# Archer.net
KiCad netlist of a schematic drawn in Altium Designer
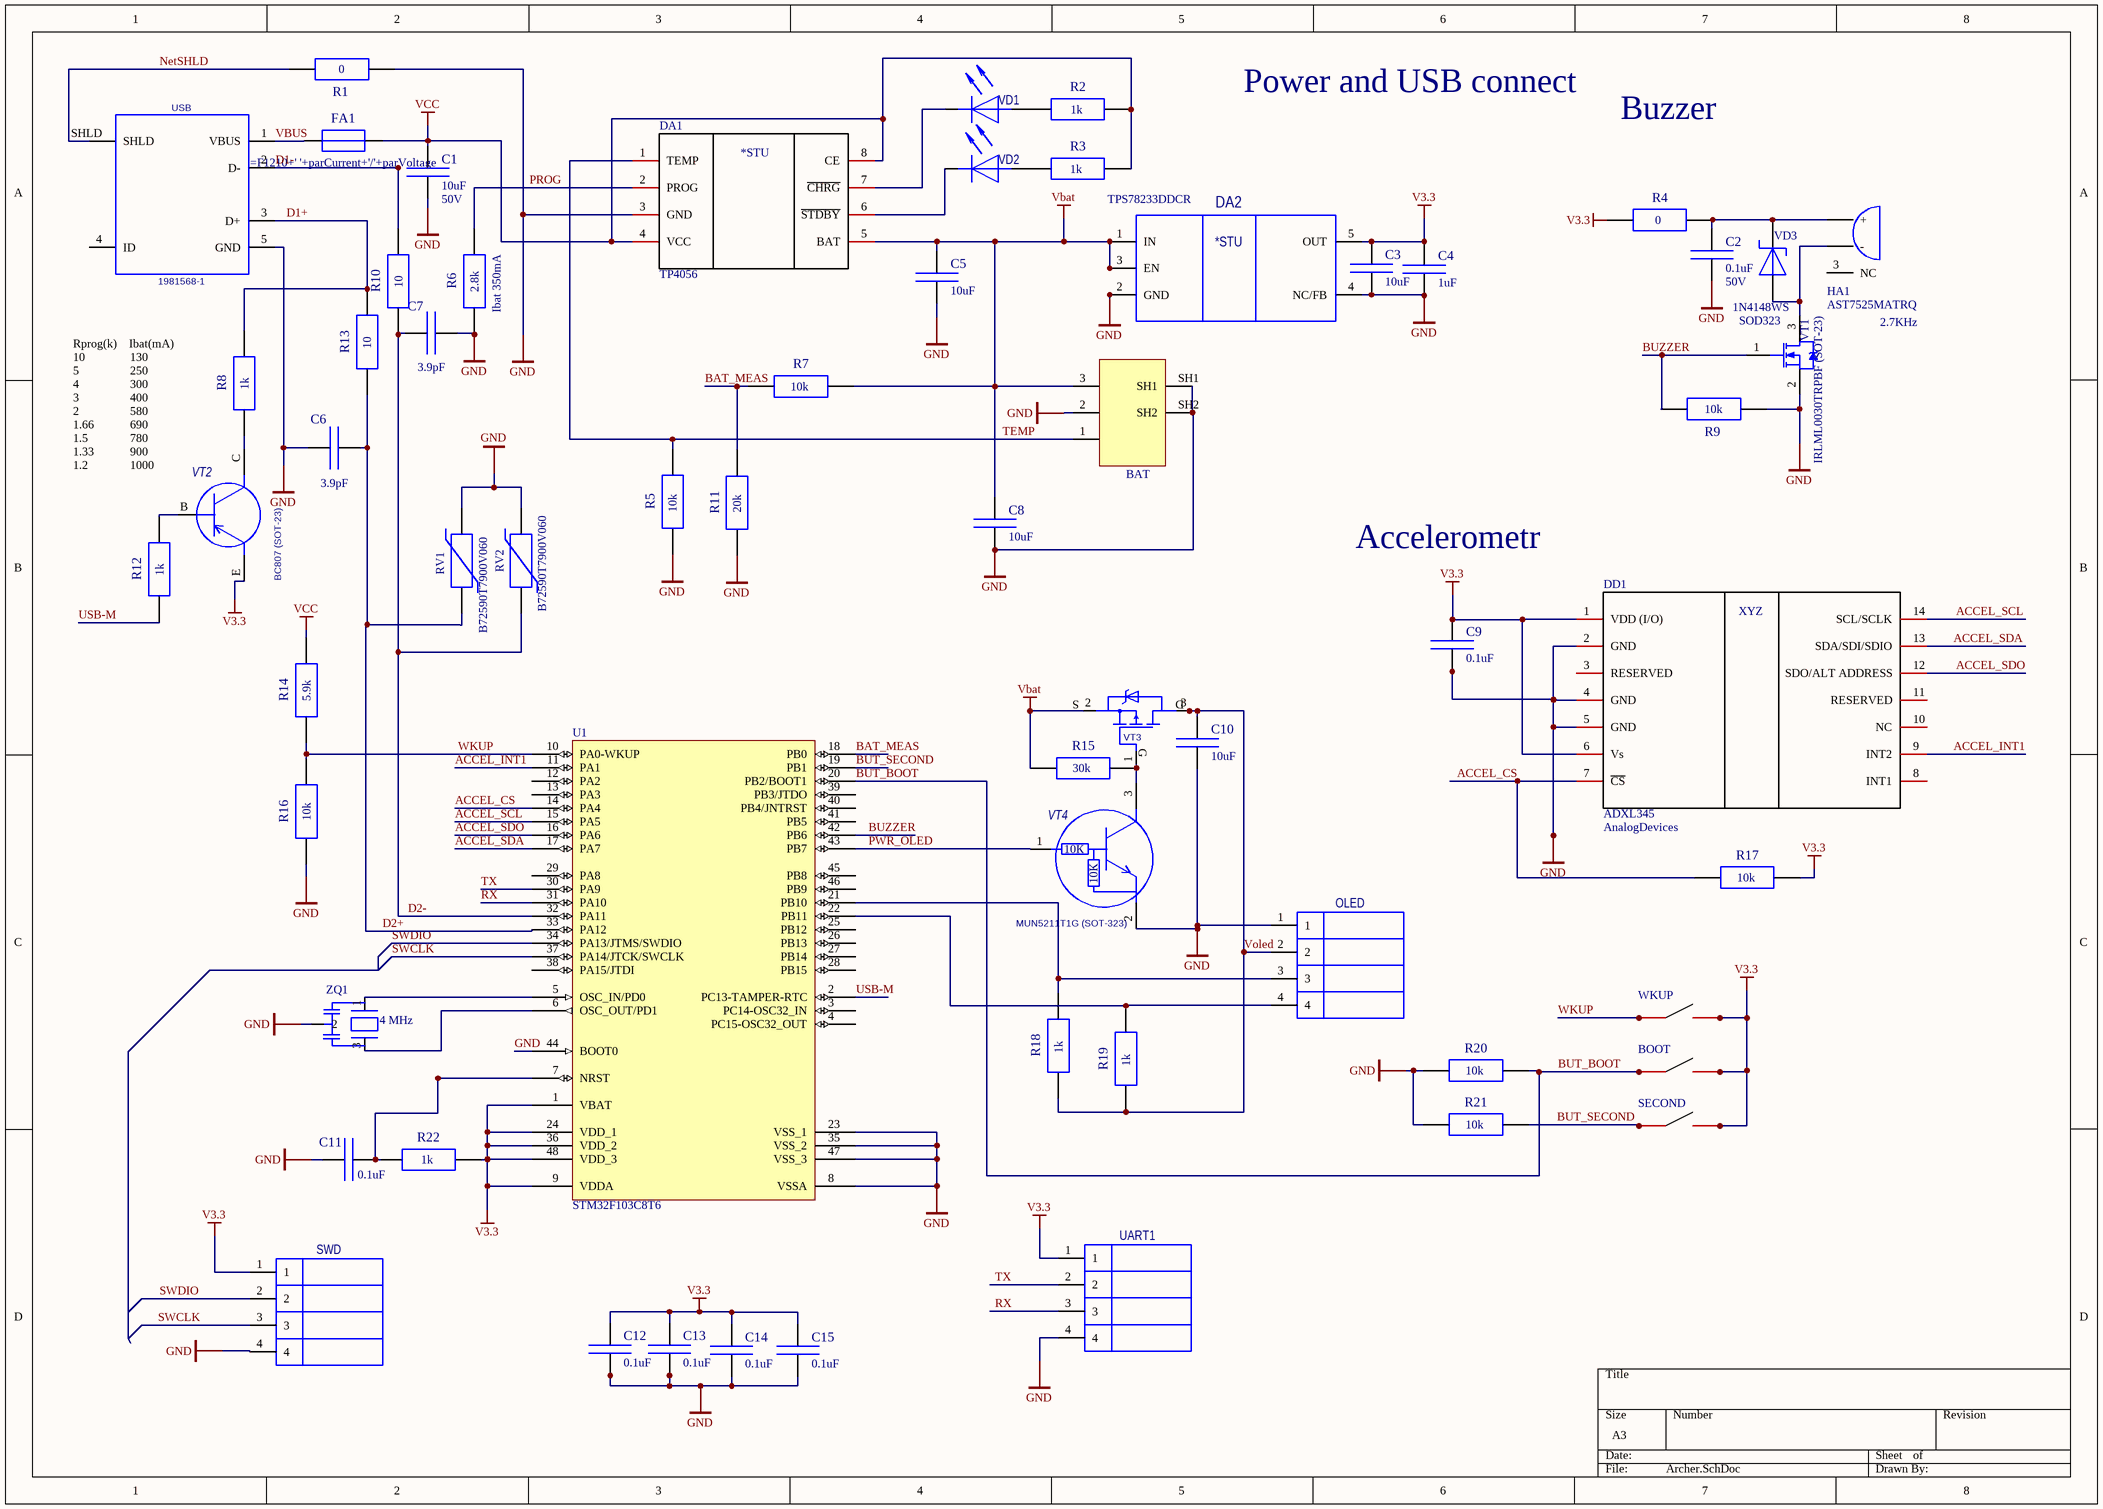
[diagram p0: Archer.SchDoc]

(export (version "E")
  (design (tool "Eeschema 10.0.6"))
  (components
    (comp (ref "BAT")
      (value "Hirose DF13A-3P-1.25H(20)")
      (footprint "DF13A-3P-1.25H")
      (description "Crimping Connector 3p")
      (fields (field (name "CMPPARTNUM") "DF13A-3P-1.25H(20)"))
      (libsource (lib "connectors") (part "DF13C-3P-1.25_(**)"))
    )
    (comp (ref "BOOT")
      (value "~")
      (footprint "Button Switronic Industrial 0650HIM-130G-G high")
      (description "Кнопка тактовая без фиксации")
      (libsource (lib "RADIOMASTER") (part "Button Switronic Industrial 0650HIM-130G-G high"))
    )
    (comp (ref "C1")
      (value "10uF")
      (footprint "CAPC3216X135(1206)")
      (description "C1206")
      (fields (field (name "PARVOLTAGE") "50V") (field (name "Comment") "чип 1206 10uF/50V, "))
      (libsource (lib "pass_smd") (part "C1206"))
    )
    (comp (ref "C2")
      (value "0.1uF")
      (footprint "CAPC1608X50(0603)")
      (description "C0603")
      (fields (field (name "PARVOLTAGE") "50V") (field (name "Comment") "чип 0603 0.1uF/50V, "))
      (libsource (lib "pass_smd") (part "C0603"))
    )
    (comp (ref "C3")
      (value "10uF")
      (footprint "CAPC3216X135(1206)")
      (description "C1206")
      (fields (field (name "Comment") "чип 1206 10uF/50V, "))
      (libsource (lib "pass_smd") (part "C1206"))
    )
    (comp (ref "C4")
      (value "1uF")
      (footprint "CAPC1608X50(0603)")
      (description "C0603")
      (fields (field (name "Comment") "чип 0603 1uF/50V, "))
      (libsource (lib "pass_smd") (part "C0603"))
    )
    (comp (ref "C5")
      (value "10uF")
      (footprint "CAPC3216X135(1206)")
      (description "C1206")
      (fields (field (name "Comment") "чип 1206 10uF/50V, "))
      (libsource (lib "pass_smd") (part "C1206"))
    )
    (comp (ref "C6")
      (value "3.9pF")
      (footprint "CAPC1608X50(0603)")
      (description "C0603")
      (fields (field (name "Comment") "чип 0603 3.9pF/50V, "))
      (libsource (lib "pass_smd") (part "C0603"))
    )
    (comp (ref "C7")
      (value "3.9pF")
      (footprint "CAPC1608X50(0603)")
      (description "C0603")
      (fields (field (name "Comment") "чип 0603 3.9pF/50V, "))
      (libsource (lib "pass_smd") (part "C0603"))
    )
    (comp (ref "C8")
      (value "10uF")
      (footprint "CAPC3216X135(1206)")
      (description "C1206")
      (fields (field (name "Comment") "чип 1206 10uF/50V, "))
      (libsource (lib "pass_smd") (part "C1206"))
    )
    (comp (ref "C9")
      (value "0.1uF")
      (footprint "CAPC1608X50(0603)")
      (description "C0603")
      (fields (field (name "Comment") "чип 0603 0.1uF/50V, "))
      (libsource (lib "pass_smd") (part "C0603"))
    )
    (comp (ref "C10")
      (value "10uF")
      (footprint "CAPC2012X135(0805)")
      (description "C0805")
      (fields (field (name "Comment") "чип 0805 10uF/50V, "))
      (libsource (lib "pass_smd") (part "C0805"))
    )
    (comp (ref "C11")
      (value "0.1uF")
      (footprint "CAPC1608X50(0603)")
      (description "C0603")
      (fields (field (name "Comment") "чип 0603 0.1uF/50V, "))
      (libsource (lib "pass_smd") (part "C0603"))
    )
    (comp (ref "C12")
      (value "0.1uF")
      (footprint "CAPC1608X50(0603)")
      (description "C0603")
      (fields (field (name "Comment") "чип 0603 0.1uF/50V, "))
      (libsource (lib "pass_smd") (part "C0603"))
    )
    (comp (ref "C13")
      (value "0.1uF")
      (footprint "CAPC1608X50(0603)")
      (description "C0603")
      (fields (field (name "Comment") "чип 0603 0.1uF/50V, "))
      (libsource (lib "pass_smd") (part "C0603"))
    )
    (comp (ref "C14")
      (value "0.1uF")
      (footprint "CAPC1608X50(0603)")
      (description "C0603")
      (fields (field (name "Comment") "чип 0603 0.1uF/50V, "))
      (libsource (lib "pass_smd") (part "C0603"))
    )
    (comp (ref "C15")
      (value "0.1uF")
      (footprint "CAPC1608X50(0603)")
      (description "C0603")
      (fields (field (name "Comment") "чип 0603 0.1uF/50V, "))
      (libsource (lib "pass_smd") (part "C0603"))
    )
    (comp (ref "DA1")
      (value "~")
      (footprint "Microchip NanJing Linear Battery Charger TP4056 SOP-8")
      (fields (field (name "MODEL NAME") "TP4056"))
      (libsource (lib "RADIOMASTER") (part "Microchip NanJing Linear Battery Charger TP4056 SOP-8"))
    )
    (comp (ref "DA2")
      (value "TPS78233DDCR(SOT23-5)")
      (footprint "SOT95P285X130-5N(SOT23-5)")
      (description "TPS76333DBV")
      (fields (field (name "CMPPARTNUM") "TPS78233DDCR"))
      (libsource (lib "TI") (part "TPS76333DBV"))
    )
    (comp (ref "DD1")
      (value "~")
      (footprint "Microchip DigitalAccelerometer AnalogDevices ADXL345 LGA-14")
      (fields (field (name "MODEL NAME") "ADXL345") (field (name "FACTORY") "AnalogDevices"))
      (libsource (lib "RADIOMASTER") (part "Microchip DigitalAccelerometer AnalogDevices ADXL345 LGA-14"))
    )
    (comp (ref "FA1")
      (value "2A/")
      (footprint "RESC1210N")
      (description "FUSE 1210")
      (libsource (lib "pass_smd") (part "FUSE 1210"))
    )
    (comp (ref "HA1")
      (value "AST7525MATRQ")
      (footprint "AST7525MATRQ")
      (description "Transducer (Electro-Mech)")
      (fields (field (name "ПРИМЕЧАНИЕ") "2.7KHz"))
      (libsource (lib "MyLib") (part "AST7525MATRQ"))
    )
    (comp (ref "OLED")
      (value "DS1021-1x4")
      (footprint "HDRV4P254_1x4")
      (description "IDC разъем 4 контактов. Шаг 2.54мм")
      (libsource (lib "connectors") (part "Header-2.54P-4N"))
    )
    (comp (ref "R1")
      (value "0")
      (footprint "RESC1608X45(0603)")
      (description "R0603")
      (fields (field (name "TOLERANCE") "5%") (field (name "Comment") "чип 0603 0 5%"))
      (libsource (lib "pass_smd") (part "R0603"))
    )
    (comp (ref "R2")
      (value "1k")
      (footprint "RESC1608X45(0603)")
      (description "R0603")
      (fields (field (name "TOLERANCE") "5%") (field (name "Comment") "чип 0603 1k 5%"))
      (libsource (lib "pass_smd") (part "R0603"))
    )
    (comp (ref "R3")
      (value "1k")
      (footprint "RESC1608X45(0603)")
      (description "R0603")
      (fields (field (name "TOLERANCE") "5%") (field (name "Comment") "чип 0603 1k 5%"))
      (libsource (lib "pass_smd") (part "R0603"))
    )
    (comp (ref "R4")
      (value "0")
      (footprint "RESC1608X45(0603)")
      (description "R0603")
      (fields (field (name "TOLERANCE") "5%") (field (name "Comment") "чип 0603 0 5%"))
      (libsource (lib "pass_smd") (part "R0603"))
    )
    (comp (ref "R5")
      (value "10k")
      (footprint "RESC1608X45(0603)")
      (description "R0603")
      (fields (field (name "TOLERANCE") "5%") (field (name "Comment") "чип 0603 10k 5%"))
      (libsource (lib "pass_smd") (part "R0603"))
    )
    (comp (ref "R6")
      (value "2.8k")
      (footprint "RESC1608X45(0603)")
      (description "R0603")
      (fields (field (name "TOLERANCE") "5%") (field (name "Comment") "чип 0603 2.8k 5%"))
      (libsource (lib "pass_smd") (part "R0603"))
    )
    (comp (ref "R7")
      (value "10k")
      (footprint "RESC1608X45(0603)")
      (description "R0603")
      (fields (field (name "TOLERANCE") "5%") (field (name "Comment") "чип 0603 10k 5%"))
      (libsource (lib "pass_smd") (part "R0603"))
    )
    (comp (ref "R8")
      (value "1k")
      (footprint "RESC1608X45(0603)")
      (description "R0603")
      (fields (field (name "TOLERANCE") "5%") (field (name "Comment") "чип 0603 1k 5%"))
      (libsource (lib "pass_smd") (part "R0603"))
    )
    (comp (ref "R9")
      (value "10k")
      (footprint "RESC1608X45(0603)")
      (description "R0603")
      (fields (field (name "TOLERANCE") "5%") (field (name "Comment") "чип 0603 10k 5%"))
      (libsource (lib "pass_smd") (part "R0603"))
    )
    (comp (ref "R10")
      (value "10")
      (footprint "RESC1608X45(0603)")
      (description "R0603")
      (fields (field (name "TOLERANCE") "5%") (field (name "Comment") "чип 0603 10 5%"))
      (libsource (lib "pass_smd") (part "R0603"))
    )
    (comp (ref "R11")
      (value "20k")
      (footprint "RESC1608X45(0603)")
      (description "R0603")
      (fields (field (name "TOLERANCE") "5%") (field (name "Comment") "чип 0603 20k 5%"))
      (libsource (lib "pass_smd") (part "R0603"))
    )
    (comp (ref "R12")
      (value "1k")
      (footprint "RESC1608X45(0603)")
      (description "R0603")
      (fields (field (name "TOLERANCE") "5%") (field (name "Comment") "чип 0603 1k 5%"))
      (libsource (lib "pass_smd") (part "R0603"))
    )
    (comp (ref "R13")
      (value "10")
      (footprint "RESC1608X45(0603)")
      (description "R0603")
      (fields (field (name "TOLERANCE") "5%") (field (name "Comment") "чип 0603 10 5%"))
      (libsource (lib "pass_smd") (part "R0603"))
    )
    (comp (ref "R14")
      (value "5.9k")
      (footprint "RESC1608X45(0603)")
      (description "R0603")
      (fields (field (name "TOLERANCE") "5%") (field (name "Comment") "чип 0603 5.9k 5%"))
      (libsource (lib "pass_smd") (part "R0603"))
    )
    (comp (ref "R15")
      (value "30k")
      (footprint "RESC1608X45(0603)")
      (description "R0603")
      (fields (field (name "TOLERANCE") "5%") (field (name "Comment") "чип 0603 30k 5%"))
      (libsource (lib "pass_smd") (part "R0603"))
    )
    (comp (ref "R16")
      (value "10k")
      (footprint "RESC1608X45(0603)")
      (description "R0603")
      (fields (field (name "TOLERANCE") "5%") (field (name "Comment") "чип 0603 10k 5%"))
      (libsource (lib "pass_smd") (part "R0603"))
    )
    (comp (ref "R17")
      (value "10k")
      (footprint "RESC1608X45(0603)")
      (description "R0603")
      (fields (field (name "TOLERANCE") "5%") (field (name "Comment") "чип 0603 10k 5%"))
      (libsource (lib "pass_smd") (part "R0603"))
    )
    (comp (ref "R18")
      (value "1k")
      (footprint "RESC1608X45(0603)")
      (description "R0603")
      (fields (field (name "TOLERANCE") "5%") (field (name "Comment") "чип 0603 1k 5%"))
      (libsource (lib "pass_smd") (part "R0603"))
    )
    (comp (ref "R19")
      (value "1k")
      (footprint "RESC1608X45(0603)")
      (description "R0603")
      (fields (field (name "TOLERANCE") "5%") (field (name "Comment") "чип 0603 1k 5%"))
      (libsource (lib "pass_smd") (part "R0603"))
    )
    (comp (ref "R20")
      (value "10k")
      (footprint "RESC1608X45(0603)")
      (description "R0603")
      (fields (field (name "TOLERANCE") "5%") (field (name "Comment") "чип 0603 10k 5%"))
      (libsource (lib "pass_smd") (part "R0603"))
    )
    (comp (ref "R21")
      (value "10k")
      (footprint "RESC1608X45(0603)")
      (description "R0603")
      (fields (field (name "TOLERANCE") "5%") (field (name "Comment") "чип 0603 10k 5%"))
      (libsource (lib "pass_smd") (part "R0603"))
    )
    (comp (ref "R22")
      (value "1k")
      (footprint "RESC1608X45(0603)")
      (description "R0603")
      (fields (field (name "TOLERANCE") "5%") (field (name "Comment") "чип 0603 1k 5%"))
      (libsource (lib "pass_smd") (part "R0603"))
    )
    (comp (ref "RV1")
      (value "B72590T7900V060")
      (footprint "RESC1005X35(0402)")
      (libsource (lib "pass_smd") (part "B72590T7900V060"))
    )
    (comp (ref "RV2")
      (value "B72590T7900V060")
      (footprint "RESC1005X35(0402)")
      (libsource (lib "pass_smd") (part "B72590T7900V060"))
    )
    (comp (ref "SECOND")
      (value "~")
      (footprint "Button Switronic Industrial 0650HIM-130G-G high")
      (description "Кнопка тактовая без фиксации")
      (libsource (lib "RADIOMASTER") (part "Button Switronic Industrial 0650HIM-130G-G high"))
    )
    (comp (ref "SWD")
      (value "DS1021-1x4")
      (footprint "HDRV4P254_1x4")
      (description "IDC разъем 4 контактов. Шаг 2.54мм")
      (libsource (lib "connectors") (part "Header-2.54P-4N"))
    )
    (comp (ref "U1")
      (value "STM32F103C8T6")
      (footprint "LQFP48_N")
      (description "STM32 ARM-based 32-bit MCU with 64 Kbytes Flash, 48-pin LQFP, Industrial Temperature")
      (fields (field (name "PUBLISHER") "Altium Limited"))
      (libsource (lib "ST Microcontroller 32-Bit STM32") (part "STM32F103C8T6"))
    )
    (comp (ref "UART1")
      (value "DS1021-1x4")
      (footprint "HDRV4P254_1x4")
      (description "IDC разъем 4 контактов. Шаг 2.54мм")
      (libsource (lib "connectors") (part "Header-2.54P-4N"))
    )
    (comp (ref "USB")
      (value "1981568-1")
      (footprint "USB MICRO-B")
      (description "USB micro type A. SMT (TE 1981568-1)")
      (libsource (lib "connectors") (part "USB Micro-B Tyco"))
    )
    (comp (ref "VD1")
      (value "чип 0603 LED (RED)")
      (footprint "LEDC1608X80N(0603)_red")
      (description "LED 0603")
      (libsource (lib "diodes") (part "LED 0603"))
    )
    (comp (ref "VD2")
      (value "чип 0603 LED (RED)")
      (footprint "LEDC1608X80N(0603)_red")
      (description "LED 0603")
      (libsource (lib "diodes") (part "LED 0603"))
    )
    (comp (ref "VD3")
      (value "1N4148WS (SOD323)")
      (footprint "SOD2514X110N(SOD323)")
      (description "BAT54WS")
      (fields (field (name "CMPPKG") "SOD323") (field (name "CMPPARTNUM") "1N4148WS"))
      (libsource (lib "diodes") (part "SOD323 SCHOTTKY"))
    )
    (comp (ref "VT1")
      (value "IRLML0030TRPBF (SOT-23)")
      (footprint "SOT95P230-3N (SOT-23) num")
      (description "HEXFET Power MOSFET")
      (fields (field (name "CMPPARTNUM") "IRLML0030TRPBF"))
      (libsource (lib "transistors") (part "IRLML0030"))
    )
    (comp (ref "VT2")
      (value "BC807 (SOT-23)")
      (footprint "SOT95P230-3N (SOT-23)")
      (description "BC807")
      (libsource (lib "transistors") (part "BC807"))
    )
    (comp (ref "VT3")
      (value "IRLML6402TRPBF (SOT-23)")
      (footprint "SOT95P230-3N (SOT-23) num")
      (description "IRLML6402")
      (fields (field (name "CMPPARTNUM") "IRLML6402TRPBF"))
      (libsource (lib "transistors") (part "IRLML6402"))
    )
    (comp (ref "VT4")
      (value "MUN5211T1G (SOT-323)")
      (footprint "SOT65P200X110-3N (SOT323)_NUM")
      (description "MUN5211T1")
      (fields
        (field (name "CMPPARTNUM") "MUN5211T1G")
        (field (name "PARR1VALUE") "10К")
        (field (name "PARR2VALUE") "10К")
      )
      (libsource (lib "transistors") (part "MUN5211T1G"))
    )
    (comp (ref "WKUP")
      (value "~")
      (footprint "Button Switronic Industrial 0650HIM-130G-G high")
      (description "Кнопка тактовая без фиксации")
      (libsource (lib "RADIOMASTER") (part "Button Switronic Industrial 0650HIM-130G-G high"))
    )
    (comp (ref "ZQ1")
      (value "4 MHz")
      (footprint "XTAL450X200X120 (CSTCR)")
      (description "CSTCR_G15C Ceramic Resonators")
      (fields (field (name "CMPPARTNUM") "CSTCR4M00G53Z-B0") (field (name "TOLERANCE") "±0.5%"))
      (libsource (lib "xtal") (part "XTAL, SMD, 4.5mm x 2mm, 3 pads"))
    )
  )
  (nets
    (net (code "1") (name "/ACCEL_CS") (class "Default")
      (node (ref "DD1") (pin "7") (pinfunction "~{CS}_7") (pintype "passive"))
      (node (ref "R17") (pin "1") (pinfunction "1_1") (pintype "passive"))
      (node (ref "U1") (pin "14") (pinfunction "PA4_14") (pintype "bidirectional"))
    )
    (net (code "2") (name "/ACCEL_INT1") (class "Default")
      (node (ref "DD1") (pin "9") (pinfunction "INT2_9") (pintype "passive"))
      (node (ref "U1") (pin "11") (pinfunction "PA1_11") (pintype "bidirectional"))
    )
    (net (code "3") (name "/ACCEL_SCL") (class "Default")
      (node (ref "DD1") (pin "14") (pinfunction "SCL/SCLK_14") (pintype "passive"))
      (node (ref "U1") (pin "15") (pinfunction "PA5_15") (pintype "bidirectional"))
    )
    (net (code "4") (name "/ACCEL_SDA") (class "Default")
      (node (ref "DD1") (pin "13") (pinfunction "SDA/SDI/SDIO_13") (pintype "passive"))
      (node (ref "U1") (pin "17") (pinfunction "PA7_17") (pintype "bidirectional"))
    )
    (net (code "5") (name "/ACCEL_SDO") (class "Default")
      (node (ref "DD1") (pin "12") (pinfunction "SDO/ALT_ADDRESS_12") (pintype "passive"))
      (node (ref "U1") (pin "16") (pinfunction "PA6_16") (pintype "bidirectional"))
    )
    (net (code "6") (name "/BAT_MEAS") (class "Default")
      (node (ref "R11") (pin "2") (pinfunction "2_2") (pintype "passive"))
      (node (ref "R7") (pin "1") (pinfunction "1_1") (pintype "passive"))
      (node (ref "U1") (pin "18") (pinfunction "PB0_18") (pintype "bidirectional"))
    )
    (net (code "7") (name "/BUT_BOOT") (class "Default")
      (node (ref "BOOT") (pin "1") (pinfunction "1_1") (pintype "passive"))
      (node (ref "BOOT") (pin "2") (pinfunction "2_2") (pintype "passive"))
      (node (ref "R20") (pin "2") (pinfunction "2_2") (pintype "passive"))
      (node (ref "U1") (pin "20") (pinfunction "PB2/BOOT1_20") (pintype "bidirectional"))
    )
    (net (code "8") (name "/BUT_SECOND") (class "Default")
      (node (ref "R21") (pin "2") (pinfunction "2_2") (pintype "passive"))
      (node (ref "SECOND") (pin "1") (pinfunction "1_1") (pintype "passive"))
      (node (ref "SECOND") (pin "2") (pinfunction "2_2") (pintype "passive"))
      (node (ref "U1") (pin "19") (pinfunction "PB1_19") (pintype "bidirectional"))
    )
    (net (code "9") (name "/BUZZER") (class "Default")
      (node (ref "R9") (pin "2") (pinfunction "2_2") (pintype "passive"))
      (node (ref "U1") (pin "42") (pinfunction "PB6_42") (pintype "bidirectional"))
      (node (ref "VT1") (pin "1") (pinfunction "G_1") (pintype "passive"))
    )
    (net (code "10") (name "/D1+") (class "Default")
      (node (ref "R13") (pin "2") (pinfunction "2_2") (pintype "passive"))
      (node (ref "R8") (pin "2") (pinfunction "2_2") (pintype "passive"))
      (node (ref "USB") (pin "3") (pinfunction "D+_3") (pintype "passive"))
    )
    (net (code "11") (name "/D1-") (class "Default")
      (node (ref "R10") (pin "2") (pinfunction "2_2") (pintype "passive"))
      (node (ref "USB") (pin "2") (pinfunction "D-_2") (pintype "passive"))
    )
    (net (code "12") (name "/D2+") (class "Default")
      (node (ref "C6") (pin "1") (pinfunction "1_1") (pintype "passive"))
      (node (ref "R13") (pin "1") (pinfunction "1_1") (pintype "passive"))
      (node (ref "RV1") (pin "2") (pinfunction "2_2") (pintype "passive"))
      (node (ref "U1") (pin "33") (pinfunction "PA12_33") (pintype "bidirectional"))
    )
    (net (code "13") (name "/D2-") (class "Default")
      (node (ref "C7") (pin "2") (pinfunction "2_2") (pintype "passive"))
      (node (ref "R10") (pin "1") (pinfunction "1_1") (pintype "passive"))
      (node (ref "RV2") (pin "2") (pinfunction "2_2") (pintype "passive"))
      (node (ref "U1") (pin "32") (pinfunction "PA11_32") (pintype "bidirectional"))
    )
    (net (code "14") (name "/NetSHLD") (class "Default")
      (node (ref "R1") (pin "2") (pinfunction "2_2") (pintype "passive"))
      (node (ref "USB") (pin "SHLD") (pinfunction "SHLD_SHLD") (pintype "passive"))
    )
    (net (code "15") (name "/PROG") (class "Default")
      (node (ref "DA1") (pin "2") (pinfunction "PROG_2") (pintype "passive"))
      (node (ref "R6") (pin "2") (pinfunction "2_2") (pintype "passive"))
    )
    (net (code "16") (name "/PWR_OLED") (class "Default")
      (node (ref "U1") (pin "43") (pinfunction "PB7_43") (pintype "bidirectional"))
      (node (ref "VT4") (pin "1") (pinfunction "B_1") (pintype "passive"))
    )
    (net (code "17") (name "/RX") (class "Default")
      (node (ref "U1") (pin "31") (pinfunction "PA10_31") (pintype "bidirectional"))
      (node (ref "UART1") (pin "3") (pinfunction "3_3") (pintype "passive"))
    )
    (net (code "18") (name "/SWCLK") (class "Default")
      (node (ref "SWD") (pin "3") (pinfunction "3_3") (pintype "passive"))
      (node (ref "U1") (pin "37") (pinfunction "PA14/JTCK/SWCLK_37") (pintype "bidirectional"))
    )
    (net (code "19") (name "/SWDIO") (class "Default")
      (node (ref "SWD") (pin "2") (pinfunction "2_2") (pintype "passive"))
      (node (ref "U1") (pin "34") (pinfunction "PA13/JTMS/SWDIO_34") (pintype "bidirectional"))
    )
    (net (code "20") (name "/TEMP") (class "Default")
      (node (ref "BAT") (pin "1") (pinfunction "1_1") (pintype "passive"))
      (node (ref "DA1") (pin "1") (pinfunction "TEMP_1") (pintype "passive"))
      (node (ref "R5") (pin "2") (pinfunction "2_2") (pintype "passive"))
    )
    (net (code "21") (name "/TX") (class "Default")
      (node (ref "U1") (pin "30") (pinfunction "PA9_30") (pintype "bidirectional"))
      (node (ref "UART1") (pin "2") (pinfunction "2_2") (pintype "passive"))
    )
    (net (code "22") (name "/USB-M") (class "Default")
      (node (ref "R12") (pin "1") (pinfunction "1_1") (pintype "passive"))
      (node (ref "U1") (pin "2") (pinfunction "PC13-TAMPER-RTC_2") (pintype "bidirectional"))
    )
    (net (code "23") (name "/VBUS") (class "Default")
      (node (ref "FA1") (pin "1") (pinfunction "1_1") (pintype "passive"))
      (node (ref "USB") (pin "1") (pinfunction "VBUS_1") (pintype "passive"))
    )
    (net (code "24") (name "/Voled") (class "Default")
      (node (ref "C10") (pin "2") (pinfunction "P2_2") (pintype "passive"))
      (node (ref "OLED") (pin "2") (pinfunction "2_2") (pintype "passive"))
      (node (ref "R18") (pin "1") (pinfunction "1_1") (pintype "passive"))
      (node (ref "R19") (pin "1") (pinfunction "1_1") (pintype "passive"))
      (node (ref "VT3") (pin "3") (pinfunction "D_3") (pintype "passive"))
    )
    (net (code "25") (name "/WKUP") (class "Default")
      (node (ref "R14") (pin "1") (pinfunction "1_1") (pintype "passive"))
      (node (ref "R16") (pin "2") (pinfunction "2_2") (pintype "passive"))
      (node (ref "U1") (pin "10") (pinfunction "PA0-WKUP_10") (pintype "bidirectional"))
      (node (ref "WKUP") (pin "1") (pinfunction "1_1") (pintype "passive"))
      (node (ref "WKUP") (pin "2") (pinfunction "2_2") (pintype "passive"))
    )
    (net (code "26") (name "GND") (class "Default")
      (node (ref "BAT") (pin "2") (pinfunction "2_2") (pintype "passive"))
      (node (ref "BAT") (pin "SH1") (pinfunction "SH1_SH1") (pintype "passive"))
      (node (ref "BAT") (pin "SH2") (pinfunction "SH2_SH2") (pintype "passive"))
      (node (ref "C1") (pin "2") (pinfunction "2_2") (pintype "passive"))
      (node (ref "C10") (pin "1") (pinfunction "P1_1") (pintype "passive"))
      (node (ref "C11") (pin "2") (pinfunction "2_2") (pintype "passive"))
      (node (ref "C12") (pin "1") (pinfunction "1_1") (pintype "passive"))
      (node (ref "C13") (pin "1") (pinfunction "1_1") (pintype "passive"))
      (node (ref "C14") (pin "1") (pinfunction "1_1") (pintype "passive"))
      (node (ref "C15") (pin "1") (pinfunction "1_1") (pintype "passive"))
      (node (ref "C2") (pin "1") (pinfunction "1_1") (pintype "passive"))
      (node (ref "C3") (pin "2") (pinfunction "2_2") (pintype "passive"))
      (node (ref "C4") (pin "1") (pinfunction "1_1") (pintype "passive"))
      (node (ref "C5") (pin "2") (pinfunction "2_2") (pintype "passive"))
      (node (ref "C6") (pin "2") (pinfunction "2_2") (pintype "passive"))
      (node (ref "C7") (pin "1") (pinfunction "1_1") (pintype "passive"))
      (node (ref "C8") (pin "2") (pinfunction "2_2") (pintype "passive"))
      (node (ref "C9") (pin "1") (pinfunction "1_1") (pintype "passive"))
      (node (ref "DA1") (pin "3") (pinfunction "GND_3") (pintype "passive"))
      (node (ref "DA2") (pin "2") (pinfunction "GND_2") (pintype "passive"))
      (node (ref "DA2") (pin "4") (pinfunction "NC/FB_4") (pintype "passive"))
      (node (ref "DD1") (pin "2") (pinfunction "GND_2") (pintype "passive"))
      (node (ref "DD1") (pin "4") (pinfunction "GND_4") (pintype "passive"))
      (node (ref "DD1") (pin "5") (pinfunction "GND_5") (pintype "passive"))
      (node (ref "OLED") (pin "1") (pinfunction "1_1") (pintype "passive"))
      (node (ref "R1") (pin "1") (pinfunction "1_1") (pintype "passive"))
      (node (ref "R11") (pin "1") (pinfunction "1_1") (pintype "passive"))
      (node (ref "R16") (pin "1") (pinfunction "1_1") (pintype "passive"))
      (node (ref "R20") (pin "1") (pinfunction "1_1") (pintype "passive"))
      (node (ref "R21") (pin "1") (pinfunction "1_1") (pintype "passive"))
      (node (ref "R5") (pin "1") (pinfunction "1_1") (pintype "passive"))
      (node (ref "R6") (pin "1") (pinfunction "1_1") (pintype "passive"))
      (node (ref "R9") (pin "1") (pinfunction "1_1") (pintype "passive"))
      (node (ref "RV1") (pin "1") (pinfunction "1_1") (pintype "passive"))
      (node (ref "RV2") (pin "1") (pinfunction "1_1") (pintype "passive"))
      (node (ref "SWD") (pin "4") (pinfunction "4_4") (pintype "passive"))
      (node (ref "U1") (pin "23") (pinfunction "VSS_1_23") (pintype "power_in"))
      (node (ref "U1") (pin "35") (pinfunction "VSS_2_35") (pintype "power_in"))
      (node (ref "U1") (pin "44") (pinfunction "BOOT0_44") (pintype "input"))
      (node (ref "U1") (pin "47") (pinfunction "VSS_3_47") (pintype "power_in"))
      (node (ref "U1") (pin "8") (pinfunction "VSSA_8") (pintype "power_in"))
      (node (ref "UART1") (pin "4") (pinfunction "4_4") (pintype "passive"))
      (node (ref "USB") (pin "5") (pinfunction "GND_5") (pintype "passive"))
      (node (ref "VT1") (pin "2") (pinfunction "S_2") (pintype "passive"))
      (node (ref "VT4") (pin "2") (pinfunction "E_2") (pintype "passive"))
      (node (ref "ZQ1") (pin "2") (pinfunction "2_2") (pintype "passive"))
    )
    (net (code "27") (name "Net-(DA1-~{CHRG})") (class "Default")
      (node (ref "DA1") (pin "7") (pinfunction "~{CHRG}_7") (pintype "passive"))
      (node (ref "VD1") (pin "C") (pinfunction "cathode_C") (pintype "passive"))
    )
    (net (code "28") (name "Net-(DA1-~{STDBY})") (class "Default")
      (node (ref "DA1") (pin "6") (pinfunction "~{STDBY}_6") (pintype "passive"))
      (node (ref "VD2") (pin "C") (pinfunction "cathode_C") (pintype "passive"))
    )
    (net (code "29") (name "Net-(HA1-+)") (class "Default")
      (node (ref "C2") (pin "2") (pinfunction "2_2") (pintype "passive"))
      (node (ref "HA1") (pin "1") (pinfunction "+_1") (pintype "passive"))
      (node (ref "R4") (pin "2") (pinfunction "2_2") (pintype "passive"))
      (node (ref "VD3") (pin "C") (pinfunction "C_C") (pintype "passive"))
    )
    (net (code "30") (name "Net-(HA1--)") (class "Default")
      (node (ref "HA1") (pin "2") (pinfunction "-_2") (pintype "passive"))
      (node (ref "VD3") (pin "A") (pinfunction "A_A") (pintype "passive"))
      (node (ref "VT1") (pin "3") (pinfunction "D_3") (pintype "passive"))
    )
    (net (code "31") (name "Net-(R8-Pad1)") (class "Default")
      (node (ref "R8") (pin "1") (pinfunction "1_1") (pintype "passive"))
      (node (ref "VT2") (pin "C") (pinfunction "C_C") (pintype "passive"))
    )
    (net (code "32") (name "Net-(R12-Pad2)") (class "Default")
      (node (ref "R12") (pin "2") (pinfunction "2_2") (pintype "passive"))
      (node (ref "VT2") (pin "B") (pinfunction "B_B") (pintype "passive"))
    )
    (net (code "33") (name "Net-(U1-NRST)") (class "Default")
      (node (ref "C11") (pin "1") (pinfunction "1_1") (pintype "passive"))
      (node (ref "R22") (pin "1") (pinfunction "1_1") (pintype "passive"))
      (node (ref "U1") (pin "7") (pinfunction "NRST_7") (pintype "bidirectional"))
    )
    (net (code "34") (name "Net-(U1-OSC_IN{slash}PD0)") (class "Default")
      (node (ref "U1") (pin "5") (pinfunction "OSC_IN/PD0_5") (pintype "input"))
      (node (ref "ZQ1") (pin "1") (pinfunction "1_1") (pintype "passive"))
    )
    (net (code "35") (name "Net-(U1-OSC_OUT{slash}PD1)") (class "Default")
      (node (ref "U1") (pin "6") (pinfunction "OSC_OUT/PD1_6") (pintype "output"))
      (node (ref "ZQ1") (pin "3") (pinfunction "3_3") (pintype "passive"))
    )
    (net (code "36") (name "Net-(U1-PB10)") (class "Default")
      (node (ref "OLED") (pin "3") (pinfunction "3_3") (pintype "passive"))
      (node (ref "R18") (pin "2") (pinfunction "2_2") (pintype "passive"))
      (node (ref "U1") (pin "21") (pinfunction "PB10_21") (pintype "bidirectional"))
    )
    (net (code "37") (name "Net-(U1-PB11)") (class "Default")
      (node (ref "OLED") (pin "4") (pinfunction "4_4") (pintype "passive"))
      (node (ref "R19") (pin "2") (pinfunction "2_2") (pintype "passive"))
      (node (ref "U1") (pin "22") (pinfunction "PB11_22") (pintype "bidirectional"))
    )
    (net (code "38") (name "Net-(VD1-anod)") (class "Default")
      (node (ref "R2") (pin "1") (pinfunction "1_1") (pintype "passive"))
      (node (ref "VD1") (pin "A") (pinfunction "anod_A") (pintype "passive"))
    )
    (net (code "39") (name "Net-(VD2-anod)") (class "Default")
      (node (ref "R3") (pin "1") (pinfunction "1_1") (pintype "passive"))
      (node (ref "VD2") (pin "A") (pinfunction "anod_A") (pintype "passive"))
    )
    (net (code "40") (name "Net-(VT3-G)") (class "Default")
      (node (ref "R15") (pin "2") (pinfunction "2_2") (pintype "passive"))
      (node (ref "VT3") (pin "1") (pinfunction "G_1") (pintype "passive"))
      (node (ref "VT4") (pin "3") (pinfunction "C_3") (pintype "passive"))
    )
    (net (code "41") (name "V3.3") (class "Default")
      (node (ref "BOOT") (pin "3") (pinfunction "3_3") (pintype "passive"))
      (node (ref "BOOT") (pin "4") (pinfunction "4_4") (pintype "passive"))
      (node (ref "C12") (pin "2") (pinfunction "2_2") (pintype "passive"))
      (node (ref "C13") (pin "2") (pinfunction "2_2") (pintype "passive"))
      (node (ref "C14") (pin "2") (pinfunction "2_2") (pintype "passive"))
      (node (ref "C15") (pin "2") (pinfunction "2_2") (pintype "passive"))
      (node (ref "C3") (pin "1") (pinfunction "1_1") (pintype "passive"))
      (node (ref "C4") (pin "2") (pinfunction "2_2") (pintype "passive"))
      (node (ref "C9") (pin "2") (pinfunction "2_2") (pintype "passive"))
      (node (ref "DA2") (pin "5") (pinfunction "OUT_5") (pintype "passive"))
      (node (ref "DD1") (pin "1") (pinfunction "VDD_(I/O)_1") (pintype "passive"))
      (node (ref "DD1") (pin "6") (pinfunction "Vs_6") (pintype "passive"))
      (node (ref "R17") (pin "2") (pinfunction "2_2") (pintype "passive"))
      (node (ref "R22") (pin "2") (pinfunction "2_2") (pintype "passive"))
      (node (ref "R4") (pin "1") (pinfunction "1_1") (pintype "passive"))
      (node (ref "SECOND") (pin "3") (pinfunction "3_3") (pintype "passive"))
      (node (ref "SECOND") (pin "4") (pinfunction "4_4") (pintype "passive"))
      (node (ref "SWD") (pin "1") (pinfunction "1_1") (pintype "passive"))
      (node (ref "U1") (pin "1") (pinfunction "VBAT_1") (pintype "power_in"))
      (node (ref "U1") (pin "24") (pinfunction "VDD_1_24") (pintype "power_in"))
      (node (ref "U1") (pin "36") (pinfunction "VDD_2_36") (pintype "power_in"))
      (node (ref "U1") (pin "48") (pinfunction "VDD_3_48") (pintype "power_in"))
      (node (ref "U1") (pin "9") (pinfunction "VDDA_9") (pintype "power_in"))
      (node (ref "UART1") (pin "1") (pinfunction "1_1") (pintype "passive"))
      (node (ref "VT2") (pin "E") (pinfunction "E_E") (pintype "passive"))
      (node (ref "WKUP") (pin "3") (pinfunction "3_3") (pintype "passive"))
      (node (ref "WKUP") (pin "4") (pinfunction "4_4") (pintype "passive"))
    )
    (net (code "42") (name "VCC") (class "Default")
      (node (ref "C1") (pin "1") (pinfunction "1_1") (pintype "passive"))
      (node (ref "DA1") (pin "4") (pinfunction "VCC_4") (pintype "passive"))
      (node (ref "DA1") (pin "8") (pinfunction "CE_8") (pintype "passive"))
      (node (ref "FA1") (pin "2") (pinfunction "2_2") (pintype "passive"))
      (node (ref "R14") (pin "2") (pinfunction "2_2") (pintype "passive"))
      (node (ref "R2") (pin "2") (pinfunction "2_2") (pintype "passive"))
      (node (ref "R3") (pin "2") (pinfunction "2_2") (pintype "passive"))
    )
    (net (code "43") (name "Vbat") (class "Default")
      (node (ref "BAT") (pin "3") (pinfunction "3_3") (pintype "passive"))
      (node (ref "C5") (pin "1") (pinfunction "1_1") (pintype "passive"))
      (node (ref "C8") (pin "1") (pinfunction "1_1") (pintype "passive"))
      (node (ref "DA1") (pin "5") (pinfunction "BAT_5") (pintype "passive"))
      (node (ref "DA2") (pin "1") (pinfunction "IN_1") (pintype "passive"))
      (node (ref "DA2") (pin "3") (pinfunction "EN_3") (pintype "passive"))
      (node (ref "R15") (pin "1") (pinfunction "1_1") (pintype "passive"))
      (node (ref "R7") (pin "2") (pinfunction "2_2") (pintype "passive"))
      (node (ref "VT3") (pin "2") (pinfunction "S_2") (pintype "passive"))
    )
    (net (code "44") (name "unconnected-(DD1-INT1-Pad8)") (class "Default")
      (node (ref "DD1") (pin "8") (pinfunction "INT1_8") (pintype "passive"))
    )
    (net (code "45") (name "unconnected-(DD1-NC-Pad10)") (class "Default")
      (node (ref "DD1") (pin "10") (pinfunction "NC_10") (pintype "passive"))
    )
    (net (code "46") (name "unconnected-(DD1-RESERVED-Pad3)") (class "Default")
      (node (ref "DD1") (pin "3") (pinfunction "RESERVED_3") (pintype "passive"))
    )
    (net (code "47") (name "unconnected-(DD1-RESERVED-Pad11)") (class "Default")
      (node (ref "DD1") (pin "11") (pinfunction "RESERVED_11") (pintype "passive"))
    )
    (net (code "48") (name "unconnected-(HA1-NC-Pad3)") (class "Default")
      (node (ref "HA1") (pin "3") (pinfunction "NC_3") (pintype "passive"))
    )
    (net (code "49") (name "unconnected-(U1-PA2-Pad12)") (class "Default")
      (node (ref "U1") (pin "12") (pinfunction "PA2_12") (pintype "bidirectional"))
    )
    (net (code "50") (name "unconnected-(U1-PA3-Pad13)") (class "Default")
      (node (ref "U1") (pin "13") (pinfunction "PA3_13") (pintype "bidirectional"))
    )
    (net (code "51") (name "unconnected-(U1-PA8-Pad29)") (class "Default")
      (node (ref "U1") (pin "29") (pinfunction "PA8_29") (pintype "bidirectional"))
    )
    (net (code "52") (name "unconnected-(U1-PA15{slash}JTDI-Pad38)") (class "Default")
      (node (ref "U1") (pin "38") (pinfunction "PA15/JTDI_38") (pintype "bidirectional"))
    )
    (net (code "53") (name "unconnected-(U1-PB3{slash}JTDO-Pad39)") (class "Default")
      (node (ref "U1") (pin "39") (pinfunction "PB3/JTDO_39") (pintype "bidirectional"))
    )
    (net (code "54") (name "unconnected-(U1-PB4{slash}JNTRST-Pad40)") (class "Default")
      (node (ref "U1") (pin "40") (pinfunction "PB4/JNTRST_40") (pintype "bidirectional"))
    )
    (net (code "55") (name "unconnected-(U1-PB5-Pad41)") (class "Default")
      (node (ref "U1") (pin "41") (pinfunction "PB5_41") (pintype "bidirectional"))
    )
    (net (code "56") (name "unconnected-(U1-PB8-Pad45)") (class "Default")
      (node (ref "U1") (pin "45") (pinfunction "PB8_45") (pintype "bidirectional"))
    )
    (net (code "57") (name "unconnected-(U1-PB9-Pad46)") (class "Default")
      (node (ref "U1") (pin "46") (pinfunction "PB9_46") (pintype "bidirectional"))
    )
    (net (code "58") (name "unconnected-(U1-PB12-Pad25)") (class "Default")
      (node (ref "U1") (pin "25") (pinfunction "PB12_25") (pintype "bidirectional"))
    )
    (net (code "59") (name "unconnected-(U1-PB13-Pad26)") (class "Default")
      (node (ref "U1") (pin "26") (pinfunction "PB13_26") (pintype "bidirectional"))
    )
    (net (code "60") (name "unconnected-(U1-PB14-Pad27)") (class "Default")
      (node (ref "U1") (pin "27") (pinfunction "PB14_27") (pintype "bidirectional"))
    )
    (net (code "61") (name "unconnected-(U1-PB15-Pad28)") (class "Default")
      (node (ref "U1") (pin "28") (pinfunction "PB15_28") (pintype "bidirectional"))
    )
    (net (code "62") (name "unconnected-(U1-PC14-OSC32_IN-Pad3)") (class "Default")
      (node (ref "U1") (pin "3") (pinfunction "PC14-OSC32_IN_3") (pintype "bidirectional"))
    )
    (net (code "63") (name "unconnected-(U1-PC15-OSC32_OUT-Pad4)") (class "Default")
      (node (ref "U1") (pin "4") (pinfunction "PC15-OSC32_OUT_4") (pintype "bidirectional"))
    )
    (net (code "64") (name "unconnected-(USB-ID-Pad4)") (class "Default")
      (node (ref "USB") (pin "4") (pinfunction "ID_4") (pintype "passive"))
    )
  )
)
